# trs.net
KiCad netlist of a schematic drawn in Altium Designer
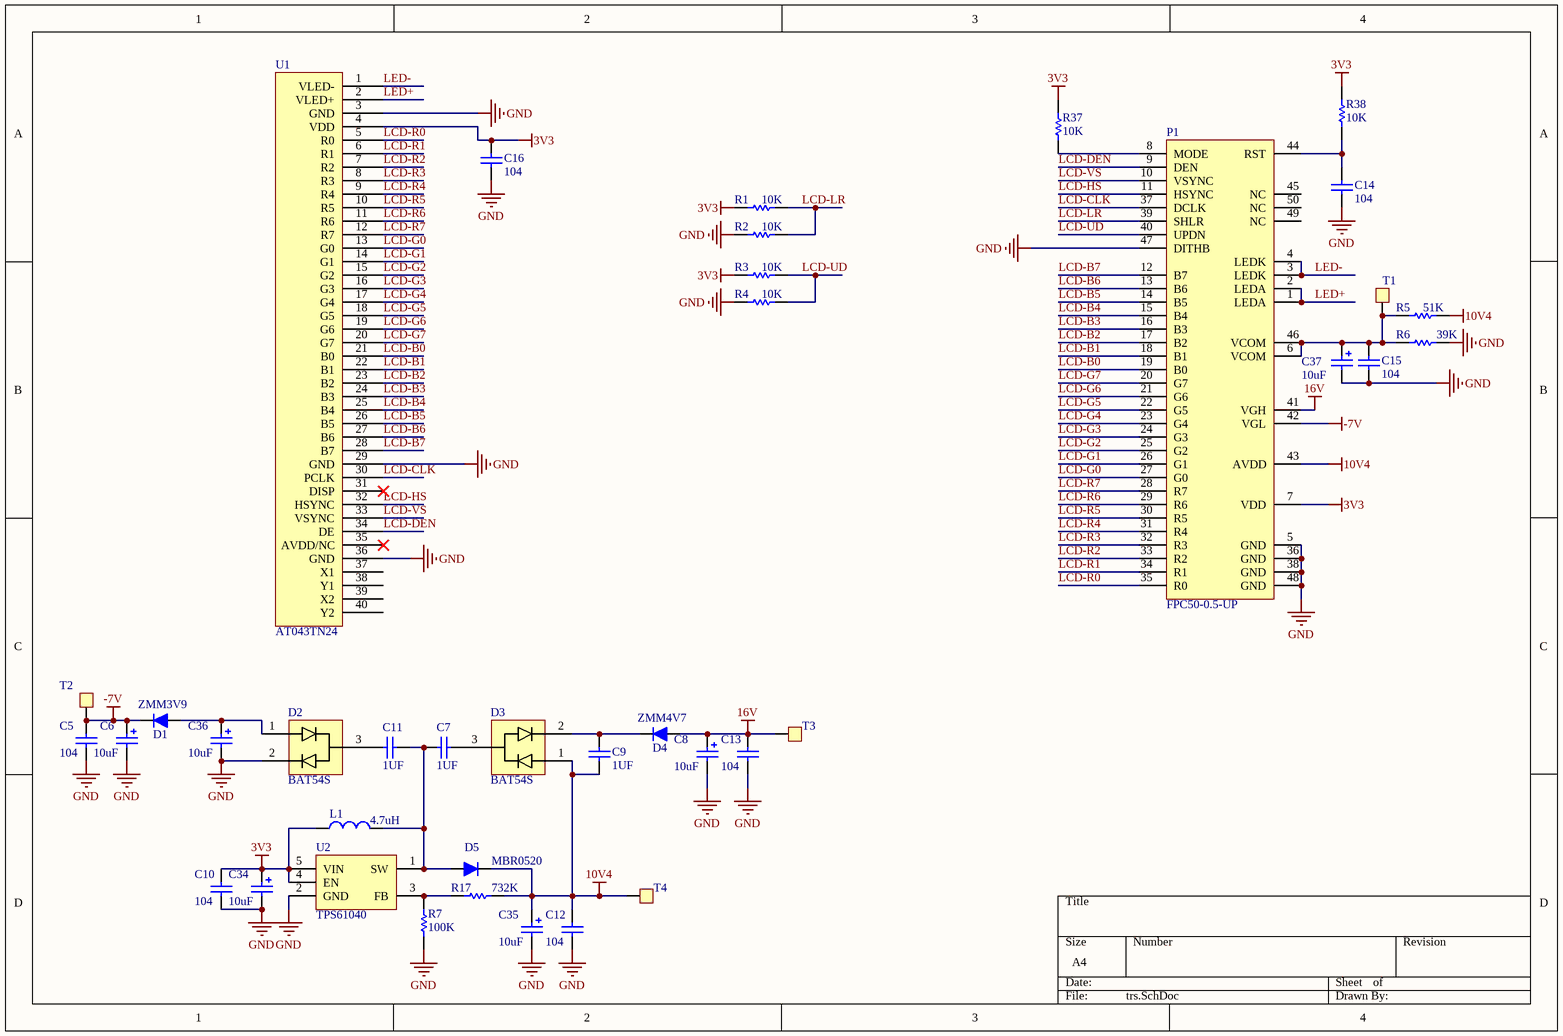
[diagram p0: trs.SchDoc]

(export (version "E")
  (design (tool "Eeschema 10.0.6"))
  (components
    (comp (ref "C5")
      (value "104")
      (footprint "0603C")
      (fields (field (name "ALTIUM_UNNAMED_1") "104"))
      (libsource (lib "OKmeSchLibrary") (part "C0.1uF"))
    )
    (comp (ref "C6")
      (value "10uF")
      (footprint "0603C")
      (description "Polarized Capacitor (Radial)")
      (fields (field (name "Comment") "C10uF") (field (name "PUBLISHER") "Altium Limited"))
      (libsource (lib "Miscellaneous Devices") (part "Cap Pol1"))
    )
    (comp (ref "C7")
      (value "C1UF")
      (footprint "0603C")
      (fields (field (name "ALTIUM_UNNAMED_1") "1UF"))
      (libsource (lib "OKmeSchLibrary") (part "C0.1uF"))
    )
    (comp (ref "C8")
      (value "10uF")
      (footprint "0603C")
      (description "Polarized Capacitor (Radial)")
      (fields (field (name "Comment") "C10uF") (field (name "PUBLISHER") "Altium Limited"))
      (libsource (lib "Miscellaneous Devices") (part "Cap Pol1"))
    )
    (comp (ref "C9")
      (value "C1UF")
      (footprint "0603C")
      (fields (field (name "ALTIUM_UNNAMED_1") "1UF"))
      (libsource (lib "OKmeSchLibrary") (part "C0.1uF"))
    )
    (comp (ref "C10")
      (value "104")
      (footprint "0603C")
      (fields (field (name "ALTIUM_UNNAMED_1") "104"))
      (libsource (lib "OKmeSchLibrary") (part "C0.1uF"))
    )
    (comp (ref "C11")
      (value "C1UF")
      (footprint "0603C")
      (fields (field (name "ALTIUM_UNNAMED_1") "1UF"))
      (libsource (lib "OKmeSchLibrary") (part "C0.1uF"))
    )
    (comp (ref "C12")
      (value "104")
      (footprint "0603C")
      (fields (field (name "ALTIUM_UNNAMED_1") "104"))
      (libsource (lib "OKmeSchLibrary") (part "C0.1uF"))
    )
    (comp (ref "C13")
      (value "104")
      (footprint "0603C")
      (fields (field (name "ALTIUM_UNNAMED_1") "104"))
      (libsource (lib "OKmeSchLibrary") (part "C0.1uF"))
    )
    (comp (ref "C14")
      (value "104")
      (footprint "0603C")
      (fields (field (name "ALTIUM_UNNAMED_1") "104"))
      (libsource (lib "OKmeSchLibrary") (part "C0.1uF"))
    )
    (comp (ref "C15")
      (value "104")
      (footprint "0603C")
      (fields (field (name "ALTIUM_UNNAMED_1") "104"))
      (libsource (lib "OKmeSchLibrary") (part "C0.1uF"))
    )
    (comp (ref "C16")
      (value "104")
      (footprint "0603C")
      (fields (field (name "ALTIUM_UNNAMED_1") "104"))
      (libsource (lib "OKmeSchLibrary") (part "C0.1uF"))
    )
    (comp (ref "C34")
      (value "10uF")
      (footprint "0603C")
      (description "Polarized Capacitor (Radial)")
      (fields (field (name "Comment") "C10uF") (field (name "PUBLISHER") "Altium Limited"))
      (libsource (lib "Miscellaneous Devices") (part "Cap Pol1"))
    )
    (comp (ref "C35")
      (value "10uF")
      (footprint "0603C")
      (description "Polarized Capacitor (Radial)")
      (fields (field (name "Comment") "C10uF") (field (name "PUBLISHER") "Altium Limited"))
      (libsource (lib "Miscellaneous Devices") (part "Cap Pol1"))
    )
    (comp (ref "C36")
      (value "10uF")
      (footprint "0603C")
      (description "Polarized Capacitor (Radial)")
      (fields (field (name "Comment") "C10uF") (field (name "PUBLISHER") "Altium Limited"))
      (libsource (lib "Miscellaneous Devices") (part "Cap Pol1"))
    )
    (comp (ref "C37")
      (value "10uF")
      (footprint "0603C")
      (description "Polarized Capacitor (Radial)")
      (fields (field (name "Comment") "C10uF") (field (name "PUBLISHER") "Altium Limited"))
      (libsource (lib "Miscellaneous Devices") (part "Cap Pol1"))
    )
    (comp (ref "D1") (value "ZMM3V9") (footprint "LL34") (libsource (lib "OKmeSchLibrary") (part "Diode")))
    (comp (ref "D2") (value "BAT54S") (footprint "SOT-23-3") (libsource (lib "") (part "BAT54S_1")))
    (comp (ref "D3") (value "BAT54S") (footprint "SOT-23-3") (libsource (lib "osc_dev") (part "BAT54S")))
    (comp (ref "D4") (value "ZMM4V7") (footprint "LL34") (libsource (lib "OKmeSchLibrary") (part "Diode")))
    (comp (ref "D5") (value "MBR0520") (footprint "SOD123") (libsource (lib "OKmeSchLibrary") (part "Diode")))
    (comp (ref "L1")
      (value "Inductor-4.7uH")
      (footprint "ins-443")
      (fields (field (name "ALTIUM_UNNAMED_1") "4.7uH"))
      (libsource (lib "OKmeSchLibrary") (part "Inductor-100uH"))
    )
    (comp (ref "P1")
      (value "FPC50-0.5-UP")
      (footprint "FPC50-0.5")
      (libsource (lib "osc_dev") (part "LCD-7-50PIN"))
    )
    (comp (ref "R1")
      (value "10K")
      (footprint "0603R")
      (fields (field (name "ALTIUM_UNNAMED_1") "10K"))
      (libsource (lib "OKmeSchLibrary") (part "R1M"))
    )
    (comp (ref "R2")
      (value "10K")
      (footprint "0603R")
      (fields (field (name "ALTIUM_UNNAMED_1") "10K"))
      (libsource (lib "OKmeSchLibrary") (part "R1M"))
    )
    (comp (ref "R3")
      (value "10K")
      (footprint "0603R")
      (fields (field (name "ALTIUM_UNNAMED_1") "10K"))
      (libsource (lib "OKmeSchLibrary") (part "R1M"))
    )
    (comp (ref "R4")
      (value "10K")
      (footprint "0603R")
      (fields (field (name "ALTIUM_UNNAMED_1") "10K"))
      (libsource (lib "OKmeSchLibrary") (part "R1M"))
    )
    (comp (ref "R5")
      (value "51K")
      (footprint "0603R")
      (fields (field (name "ALTIUM_UNNAMED_1") "51K"))
      (libsource (lib "OKmeSchLibrary") (part "R1M"))
    )
    (comp (ref "R6")
      (value "39K")
      (footprint "0603R")
      (fields (field (name "ALTIUM_UNNAMED_1") "39K"))
      (libsource (lib "OKmeSchLibrary") (part "R1M"))
    )
    (comp (ref "R7")
      (value "100K")
      (footprint "0603R")
      (fields (field (name "ALTIUM_UNNAMED_1") "100K"))
      (libsource (lib "OKmeSchLibrary") (part "R1M"))
    )
    (comp (ref "R17")
      (value "R732K")
      (footprint "0603R")
      (fields (field (name "ALTIUM_UNNAMED_1") "732K"))
      (libsource (lib "OKmeSchLibrary") (part "R1M"))
    )
    (comp (ref "R37")
      (value "10K")
      (footprint "0603R")
      (fields (field (name "ALTIUM_UNNAMED_1") "10K"))
      (libsource (lib "OKmeSchLibrary") (part "R1M"))
    )
    (comp (ref "R38")
      (value "10K")
      (footprint "0603R")
      (fields (field (name "ALTIUM_UNNAMED_1") "10K"))
      (libsource (lib "OKmeSchLibrary") (part "R1M"))
    )
    (comp (ref "T1") (value "TP") (footprint "TEST_POINT") (libsource (lib "OKmeSchLibrary") (part "TP")))
    (comp (ref "T2") (value "TP") (footprint "TEST_POINT") (libsource (lib "OKmeSchLibrary") (part "TP")))
    (comp (ref "T3") (value "TP") (footprint "TEST_POINT") (libsource (lib "") (part "TP_1")))
    (comp (ref "T4") (value "TP") (footprint "TEST_POINT") (libsource (lib "") (part "TP_1")))
    (comp (ref "U1")
      (value "AT043TN24")
      (footprint "FPC40-N")
      (libsource (lib "OKmeSchLibrary") (part "AT043TN24"))
    )
    (comp (ref "U2") (value "TPS61040") (footprint "SOT23-5") (libsource (lib "osc_dev") (part "TPS61040")))
  )
  (nets
    (net (code "1") (name "-7V") (class "Default")
      (node (ref "C5") (pin "1") (pinfunction "1_1") (pintype "passive"))
      (node (ref "C6") (pin "1") (pinfunction "1_1") (pintype "passive"))
      (node (ref "D1") (pin "2") (pinfunction "K_2") (pintype "passive"))
      (node (ref "P1") (pin "42") (pinfunction "VGL_42") (pintype "passive"))
      (node (ref "T2") (pin "1") (pinfunction "R_1") (pintype "passive"))
    )
    (net (code "2") (name "/LCD-B0") (class "Default")
      (node (ref "P1") (pin "19") (pinfunction "B0_19") (pintype "passive"))
      (node (ref "U1") (pin "21") (pinfunction "B0_21") (pintype "passive"))
    )
    (net (code "3") (name "/LCD-B1") (class "Default")
      (node (ref "P1") (pin "18") (pinfunction "B1_18") (pintype "passive"))
      (node (ref "U1") (pin "22") (pinfunction "B1_22") (pintype "passive"))
    )
    (net (code "4") (name "/LCD-B2") (class "Default")
      (node (ref "P1") (pin "17") (pinfunction "B2_17") (pintype "passive"))
      (node (ref "U1") (pin "23") (pinfunction "B2_23") (pintype "passive"))
    )
    (net (code "5") (name "/LCD-B3") (class "Default")
      (node (ref "P1") (pin "16") (pinfunction "B3_16") (pintype "passive"))
      (node (ref "U1") (pin "24") (pinfunction "B3_24") (pintype "passive"))
    )
    (net (code "6") (name "/LCD-B4") (class "Default")
      (node (ref "P1") (pin "15") (pinfunction "B4_15") (pintype "passive"))
      (node (ref "U1") (pin "25") (pinfunction "B4_25") (pintype "passive"))
    )
    (net (code "7") (name "/LCD-B5") (class "Default")
      (node (ref "P1") (pin "14") (pinfunction "B5_14") (pintype "passive"))
      (node (ref "U1") (pin "26") (pinfunction "B5_26") (pintype "passive"))
    )
    (net (code "8") (name "/LCD-B6") (class "Default")
      (node (ref "P1") (pin "13") (pinfunction "B6_13") (pintype "passive"))
      (node (ref "U1") (pin "27") (pinfunction "B6_27") (pintype "passive"))
    )
    (net (code "9") (name "/LCD-B7") (class "Default")
      (node (ref "P1") (pin "12") (pinfunction "B7_12") (pintype "passive"))
      (node (ref "U1") (pin "28") (pinfunction "B7_28") (pintype "passive"))
    )
    (net (code "10") (name "/LCD-CLK") (class "Default")
      (node (ref "P1") (pin "37") (pinfunction "DCLK_37") (pintype "passive"))
      (node (ref "U1") (pin "30") (pinfunction "PCLK_30") (pintype "passive"))
    )
    (net (code "11") (name "/LCD-DEN") (class "Default")
      (node (ref "P1") (pin "9") (pinfunction "DEN_9") (pintype "passive"))
      (node (ref "U1") (pin "34") (pinfunction "DE_34") (pintype "passive"))
    )
    (net (code "12") (name "/LCD-G0") (class "Default")
      (node (ref "P1") (pin "27") (pinfunction "G0_27") (pintype "passive"))
      (node (ref "U1") (pin "13") (pinfunction "G0_13") (pintype "passive"))
    )
    (net (code "13") (name "/LCD-G1") (class "Default")
      (node (ref "P1") (pin "26") (pinfunction "G1_26") (pintype "passive"))
      (node (ref "U1") (pin "14") (pinfunction "G1_14") (pintype "passive"))
    )
    (net (code "14") (name "/LCD-G2") (class "Default")
      (node (ref "P1") (pin "25") (pinfunction "G2_25") (pintype "passive"))
      (node (ref "U1") (pin "15") (pinfunction "G2_15") (pintype "passive"))
    )
    (net (code "15") (name "/LCD-G3") (class "Default")
      (node (ref "P1") (pin "24") (pinfunction "G3_24") (pintype "passive"))
      (node (ref "U1") (pin "16") (pinfunction "G3_16") (pintype "passive"))
    )
    (net (code "16") (name "/LCD-G4") (class "Default")
      (node (ref "P1") (pin "23") (pinfunction "G4_23") (pintype "passive"))
      (node (ref "U1") (pin "17") (pinfunction "G4_17") (pintype "passive"))
    )
    (net (code "17") (name "/LCD-G5") (class "Default")
      (node (ref "P1") (pin "22") (pinfunction "G5_22") (pintype "passive"))
      (node (ref "U1") (pin "18") (pinfunction "G5_18") (pintype "passive"))
    )
    (net (code "18") (name "/LCD-G6") (class "Default")
      (node (ref "P1") (pin "21") (pinfunction "G6_21") (pintype "passive"))
      (node (ref "U1") (pin "19") (pinfunction "G6_19") (pintype "passive"))
    )
    (net (code "19") (name "/LCD-G7") (class "Default")
      (node (ref "P1") (pin "20") (pinfunction "G7_20") (pintype "passive"))
      (node (ref "U1") (pin "20") (pinfunction "G7_20") (pintype "passive"))
    )
    (net (code "20") (name "/LCD-HS") (class "Default")
      (node (ref "P1") (pin "11") (pinfunction "HSYNC_11") (pintype "passive"))
      (node (ref "U1") (pin "32") (pinfunction "HSYNC_32") (pintype "passive"))
    )
    (net (code "21") (name "/LCD-LR") (class "Default")
      (node (ref "P1") (pin "39") (pinfunction "SHLR_39") (pintype "passive"))
      (node (ref "R1") (pin "1") (pinfunction "1_1") (pintype "passive"))
      (node (ref "R2") (pin "1") (pinfunction "1_1") (pintype "passive"))
    )
    (net (code "22") (name "/LCD-R0") (class "Default")
      (node (ref "P1") (pin "35") (pinfunction "R0_35") (pintype "passive"))
      (node (ref "U1") (pin "5") (pinfunction "R0_5") (pintype "passive"))
    )
    (net (code "23") (name "/LCD-R1") (class "Default")
      (node (ref "P1") (pin "34") (pinfunction "R1_34") (pintype "passive"))
      (node (ref "U1") (pin "6") (pinfunction "R1_6") (pintype "passive"))
    )
    (net (code "24") (name "/LCD-R2") (class "Default")
      (node (ref "P1") (pin "33") (pinfunction "R2_33") (pintype "passive"))
      (node (ref "U1") (pin "7") (pinfunction "R2_7") (pintype "passive"))
    )
    (net (code "25") (name "/LCD-R3") (class "Default")
      (node (ref "P1") (pin "32") (pinfunction "R3_32") (pintype "passive"))
      (node (ref "U1") (pin "8") (pinfunction "R3_8") (pintype "passive"))
    )
    (net (code "26") (name "/LCD-R4") (class "Default")
      (node (ref "P1") (pin "31") (pinfunction "R4_31") (pintype "passive"))
      (node (ref "U1") (pin "9") (pinfunction "R4_9") (pintype "passive"))
    )
    (net (code "27") (name "/LCD-R5") (class "Default")
      (node (ref "P1") (pin "30") (pinfunction "R5_30") (pintype "passive"))
      (node (ref "U1") (pin "10") (pinfunction "R5_10") (pintype "passive"))
    )
    (net (code "28") (name "/LCD-R6") (class "Default")
      (node (ref "P1") (pin "29") (pinfunction "R6_29") (pintype "passive"))
      (node (ref "U1") (pin "11") (pinfunction "R6_11") (pintype "passive"))
    )
    (net (code "29") (name "/LCD-R7") (class "Default")
      (node (ref "P1") (pin "28") (pinfunction "R7_28") (pintype "passive"))
      (node (ref "U1") (pin "12") (pinfunction "R7_12") (pintype "passive"))
    )
    (net (code "30") (name "/LCD-UD") (class "Default")
      (node (ref "P1") (pin "40") (pinfunction "UPDN_40") (pintype "passive"))
      (node (ref "R3") (pin "1") (pinfunction "1_1") (pintype "passive"))
      (node (ref "R4") (pin "1") (pinfunction "1_1") (pintype "passive"))
    )
    (net (code "31") (name "/LCD-VS") (class "Default")
      (node (ref "P1") (pin "10") (pinfunction "VSYNC_10") (pintype "passive"))
      (node (ref "U1") (pin "33") (pinfunction "VSYNC_33") (pintype "passive"))
    )
    (net (code "32") (name "/LED+") (class "Default")
      (node (ref "P1") (pin "1") (pinfunction "LEDA_1") (pintype "passive"))
      (node (ref "P1") (pin "2") (pinfunction "LEDA_2") (pintype "passive"))
      (node (ref "U1") (pin "2") (pinfunction "VLED+_2") (pintype "passive"))
    )
    (net (code "33") (name "/LED-") (class "Default")
      (node (ref "P1") (pin "3") (pinfunction "LEDK_3") (pintype "passive"))
      (node (ref "P1") (pin "4") (pinfunction "LEDK_4") (pintype "passive"))
      (node (ref "U1") (pin "1") (pinfunction "VLED-_1") (pintype "passive"))
    )
    (net (code "34") (name "3V3") (class "Default")
      (node (ref "C10") (pin "1") (pinfunction "1_1") (pintype "passive"))
      (node (ref "C16") (pin "2") (pinfunction "2_2") (pintype "passive"))
      (node (ref "C34") (pin "1") (pinfunction "1_1") (pintype "passive"))
      (node (ref "L1") (pin "1") (pinfunction "1_1") (pintype "passive"))
      (node (ref "P1") (pin "7") (pinfunction "VDD_7") (pintype "passive"))
      (node (ref "R1") (pin "2") (pinfunction "2_2") (pintype "passive"))
      (node (ref "R3") (pin "2") (pinfunction "2_2") (pintype "passive"))
      (node (ref "R37") (pin "2") (pinfunction "2_2") (pintype "passive"))
      (node (ref "R38") (pin "2") (pinfunction "2_2") (pintype "passive"))
      (node (ref "U1") (pin "4") (pinfunction "VDD_4") (pintype "passive"))
      (node (ref "U2") (pin "4") (pinfunction "EN_4") (pintype "passive"))
      (node (ref "U2") (pin "5") (pinfunction "VIN_5") (pintype "passive"))
    )
    (net (code "35") (name "10V4") (class "Default")
      (node (ref "C12") (pin "1") (pinfunction "1_1") (pintype "passive"))
      (node (ref "C35") (pin "1") (pinfunction "1_1") (pintype "passive"))
      (node (ref "C9") (pin "1") (pinfunction "1_1") (pintype "passive"))
      (node (ref "D3") (pin "1") (pinfunction "1_1") (pintype "passive"))
      (node (ref "D5") (pin "2") (pinfunction "K_2") (pintype "passive"))
      (node (ref "P1") (pin "43") (pinfunction "AVDD_43") (pintype "passive"))
      (node (ref "R17") (pin "2") (pinfunction "2_2") (pintype "passive"))
      (node (ref "R5") (pin "1") (pinfunction "1_1") (pintype "passive"))
      (node (ref "T4") (pin "1") (pinfunction "R_1") (pintype "passive"))
    )
    (net (code "36") (name "16V") (class "Default")
      (node (ref "C13") (pin "1") (pinfunction "1_1") (pintype "passive"))
      (node (ref "C8") (pin "1") (pinfunction "1_1") (pintype "passive"))
      (node (ref "D4") (pin "1") (pinfunction "A_1") (pintype "passive"))
      (node (ref "P1") (pin "41") (pinfunction "VGH_41") (pintype "passive"))
      (node (ref "T3") (pin "1") (pinfunction "R_1") (pintype "passive"))
    )
    (net (code "37") (name "GND") (class "Default")
      (node (ref "C10") (pin "2") (pinfunction "2_2") (pintype "passive"))
      (node (ref "C12") (pin "2") (pinfunction "2_2") (pintype "passive"))
      (node (ref "C13") (pin "2") (pinfunction "2_2") (pintype "passive"))
      (node (ref "C14") (pin "1") (pinfunction "1_1") (pintype "passive"))
      (node (ref "C15") (pin "1") (pinfunction "1_1") (pintype "passive"))
      (node (ref "C16") (pin "1") (pinfunction "1_1") (pintype "passive"))
      (node (ref "C34") (pin "2") (pinfunction "2_2") (pintype "passive"))
      (node (ref "C35") (pin "2") (pinfunction "2_2") (pintype "passive"))
      (node (ref "C36") (pin "2") (pinfunction "2_2") (pintype "passive"))
      (node (ref "C37") (pin "2") (pinfunction "2_2") (pintype "passive"))
      (node (ref "C5") (pin "2") (pinfunction "2_2") (pintype "passive"))
      (node (ref "C6") (pin "2") (pinfunction "2_2") (pintype "passive"))
      (node (ref "C8") (pin "2") (pinfunction "2_2") (pintype "passive"))
      (node (ref "D2") (pin "2") (pinfunction "2_2") (pintype "passive"))
      (node (ref "P1") (pin "36") (pinfunction "GND_36") (pintype "passive"))
      (node (ref "P1") (pin "38") (pinfunction "GND_38") (pintype "passive"))
      (node (ref "P1") (pin "47") (pinfunction "DITHB_47") (pintype "passive"))
      (node (ref "P1") (pin "48") (pinfunction "GND_48") (pintype "passive"))
      (node (ref "P1") (pin "5") (pinfunction "GND_5") (pintype "passive"))
      (node (ref "R2") (pin "2") (pinfunction "2_2") (pintype "passive"))
      (node (ref "R4") (pin "2") (pinfunction "2_2") (pintype "passive"))
      (node (ref "R6") (pin "1") (pinfunction "1_1") (pintype "passive"))
      (node (ref "R7") (pin "1") (pinfunction "1_1") (pintype "passive"))
      (node (ref "U1") (pin "29") (pinfunction "GND_29") (pintype "passive"))
      (node (ref "U1") (pin "3") (pinfunction "GND_3") (pintype "passive"))
      (node (ref "U1") (pin "36") (pinfunction "GND_36") (pintype "passive"))
      (node (ref "U2") (pin "2") (pinfunction "GND_2") (pintype "passive"))
    )
    (net (code "38") (name "Net-(C7-Pad2)") (class "Default")
      (node (ref "C7") (pin "2") (pinfunction "2_2") (pintype "passive"))
      (node (ref "D3") (pin "3") (pinfunction "3_3") (pintype "passive"))
    )
    (net (code "39") (name "Net-(C11-Pad1)") (class "Default")
      (node (ref "C11") (pin "1") (pinfunction "1_1") (pintype "passive"))
      (node (ref "D2") (pin "3") (pinfunction "3_3") (pintype "passive"))
    )
    (net (code "40") (name "Net-(D1-A)") (class "Default")
      (node (ref "C36") (pin "1") (pinfunction "1_1") (pintype "passive"))
      (node (ref "D1") (pin "1") (pinfunction "A_1") (pintype "passive"))
      (node (ref "D2") (pin "1") (pinfunction "1_1") (pintype "passive"))
    )
    (net (code "41") (name "Net-(D4-K)") (class "Default")
      (node (ref "C9") (pin "2") (pinfunction "2_2") (pintype "passive"))
      (node (ref "D3") (pin "2") (pinfunction "2_2") (pintype "passive"))
      (node (ref "D4") (pin "2") (pinfunction "K_2") (pintype "passive"))
    )
    (net (code "42") (name "Net-(D5-A)") (class "Default")
      (node (ref "C11") (pin "2") (pinfunction "2_2") (pintype "passive"))
      (node (ref "C7") (pin "1") (pinfunction "1_1") (pintype "passive"))
      (node (ref "D5") (pin "1") (pinfunction "A_1") (pintype "passive"))
      (node (ref "L1") (pin "2") (pinfunction "2_2") (pintype "passive"))
      (node (ref "U2") (pin "1") (pinfunction "SW_1") (pintype "passive"))
    )
    (net (code "43") (name "Net-(P1-MODE)") (class "Default")
      (node (ref "P1") (pin "8") (pinfunction "MODE_8") (pintype "passive"))
      (node (ref "R37") (pin "1") (pinfunction "1_1") (pintype "passive"))
    )
    (net (code "44") (name "Net-(P1-RST)") (class "Default")
      (node (ref "C14") (pin "2") (pinfunction "2_2") (pintype "passive"))
      (node (ref "P1") (pin "44") (pinfunction "RST_44") (pintype "passive"))
      (node (ref "R38") (pin "1") (pinfunction "1_1") (pintype "passive"))
    )
    (net (code "45") (name "Net-(T1-R)") (class "Default")
      (node (ref "C15") (pin "2") (pinfunction "2_2") (pintype "passive"))
      (node (ref "C37") (pin "1") (pinfunction "1_1") (pintype "passive"))
      (node (ref "P1") (pin "46") (pinfunction "VCOM_46") (pintype "passive"))
      (node (ref "P1") (pin "6") (pinfunction "VCOM_6") (pintype "passive"))
      (node (ref "R5") (pin "2") (pinfunction "2_2") (pintype "passive"))
      (node (ref "R6") (pin "2") (pinfunction "2_2") (pintype "passive"))
      (node (ref "T1") (pin "1") (pinfunction "R_1") (pintype "passive"))
    )
    (net (code "46") (name "Net-(U2-FB)") (class "Default")
      (node (ref "R17") (pin "1") (pinfunction "1_1") (pintype "passive"))
      (node (ref "R7") (pin "2") (pinfunction "2_2") (pintype "passive"))
      (node (ref "U2") (pin "3") (pinfunction "FB_3") (pintype "passive"))
    )
    (net (code "47") (name "unconnected-(P1-NC-Pad45)") (class "Default")
      (node (ref "P1") (pin "45") (pinfunction "NC_45") (pintype "passive"))
    )
    (net (code "48") (name "unconnected-(P1-NC-Pad49)") (class "Default")
      (node (ref "P1") (pin "49") (pinfunction "NC_49") (pintype "passive"))
    )
    (net (code "49") (name "unconnected-(P1-NC-Pad50)") (class "Default")
      (node (ref "P1") (pin "50") (pinfunction "NC_50") (pintype "passive"))
    )
    (net (code "50") (name "unconnected-(U1-AVDD{slash}NC-Pad35)") (class "Default")
      (node (ref "U1") (pin "35") (pinfunction "AVDD/NC_35") (pintype "passive+no_connect"))
    )
    (net (code "51") (name "unconnected-(U1-DISP-Pad31)") (class "Default")
      (node (ref "U1") (pin "31") (pinfunction "DISP_31") (pintype "passive+no_connect"))
    )
    (net (code "52") (name "unconnected-(U1-X1-Pad37)") (class "Default")
      (node (ref "U1") (pin "37") (pinfunction "X1_37") (pintype "passive"))
    )
    (net (code "53") (name "unconnected-(U1-X2-Pad39)") (class "Default")
      (node (ref "U1") (pin "39") (pinfunction "X2_39") (pintype "passive"))
    )
    (net (code "54") (name "unconnected-(U1-Y1-Pad38)") (class "Default")
      (node (ref "U1") (pin "38") (pinfunction "Y1_38") (pintype "passive"))
    )
    (net (code "55") (name "unconnected-(U1-Y2-Pad40)") (class "Default")
      (node (ref "U1") (pin "40") (pinfunction "Y2_40") (pintype "passive"))
    )
  )
)
